# GD_Power_Meter_3.net
KiCad netlist of a schematic drawn in Altium Designer
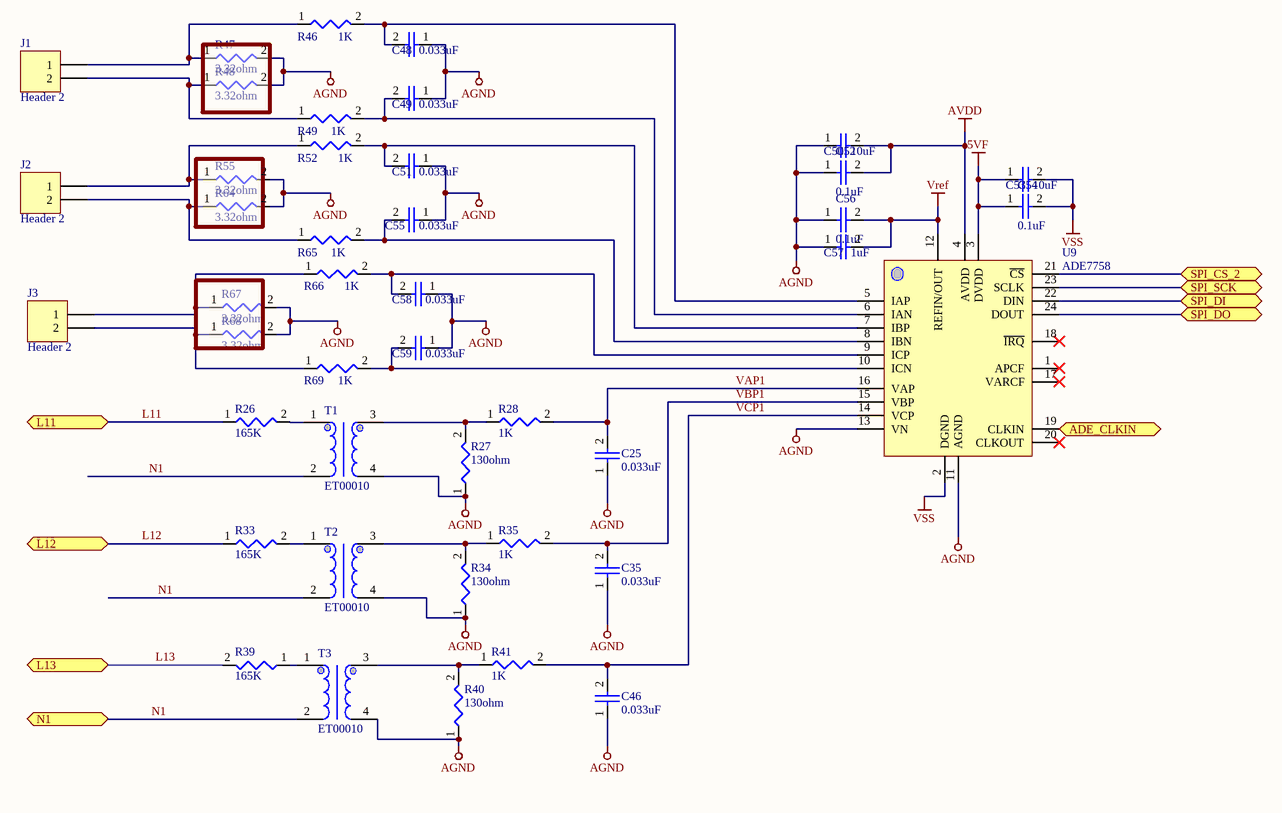
[diagram p0: GD_Power_Meter_3.SchDoc]

(export (version "E")
  (design (tool "Eeschema 10.0.6"))
  (components
    (comp (ref "C25")
      (value "0.033uF")
      (footprint "C0805")
      (description "CAP SMD X7R 50V 10% 0.033uF 0805 ROHS")
      (fields (field (name "MANUFACTURER") "Murata") (field (name "Comment") "CAP"))
      (libsource (lib "enlogic") (part "CAP"))
    )
    (comp (ref "C35")
      (value "0.033uF")
      (footprint "C0805")
      (description "CAP SMD X7R 50V 10% 0.033uF 0805 ROHS")
      (fields (field (name "MANUFACTURER") "Murata") (field (name "Comment") "CAP"))
      (libsource (lib "enlogic") (part "CAP"))
    )
    (comp (ref "C46")
      (value "0.033uF")
      (footprint "C0805")
      (description "CAP SMD X7R 50V 10% 0.033uF 0805 ROHS")
      (fields (field (name "MANUFACTURER") "Murata") (field (name "Comment") "CAP"))
      (libsource (lib "enlogic") (part "CAP"))
    )
    (comp (ref "C48")
      (value "0.033uF")
      (footprint "C0805")
      (description "CAP SMD X7R 50V 10% 0.033uF 0805 ROHS")
      (fields (field (name "MANUFACTURER") "Murata") (field (name "Comment") "CAP"))
      (libsource (lib "enlogic") (part "CAP"))
    )
    (comp (ref "C49")
      (value "0.033uF")
      (footprint "C0805")
      (description "CAP SMD X7R 50V 10% 0.033uF 0805 ROHS")
      (fields (field (name "MANUFACTURER") "Murata") (field (name "Comment") "CAP"))
      (libsource (lib "enlogic") (part "CAP"))
    )
    (comp (ref "C50")
      (value "10uF")
      (footprint "C0805")
      (description "CAP SMD CR X5R 16V 10% 10uF 0805 ROHS")
      (fields (field (name "MANUFACTURER") "Murata"))
      (libsource (lib "enlogic") (part "CAP"))
    )
    (comp (ref "C51")
      (value "0.033uF")
      (footprint "C0805")
      (description "CAP SMD X7R 50V 10% 0.033uF 0805 ROHS")
      (fields (field (name "MANUFACTURER") "Murata") (field (name "Comment") "CAP"))
      (libsource (lib "enlogic") (part "CAP"))
    )
    (comp (ref "C52")
      (value "0.1uF")
      (footprint "C0805")
      (description "CAP SMD CR X7R 50V 10% 0.1uF 0805 ROHS")
      (fields (field (name "MANUFACTURER") "YAGEO") (field (name "Comment") "CAP"))
      (libsource (lib "enlogic") (part "CAP"))
    )
    (comp (ref "C53")
      (value "10uF")
      (footprint "C0805")
      (description "CAP SMD CR X5R 16V 10% 10uF 0805 ROHS")
      (fields (field (name "MANUFACTURER") "Murata"))
      (libsource (lib "enlogic") (part "CAP"))
    )
    (comp (ref "C54")
      (value "0.1uF")
      (footprint "C0805")
      (description "CAP SMD CR X7R 50V 10% 0.1uF 0805 ROHS")
      (fields (field (name "MANUFACTURER") "YAGEO") (field (name "Comment") "CAP"))
      (libsource (lib "enlogic") (part "CAP"))
    )
    (comp (ref "C55")
      (value "0.033uF")
      (footprint "C0805")
      (description "CAP SMD X7R 50V 10% 0.033uF 0805 ROHS")
      (fields (field (name "MANUFACTURER") "Murata") (field (name "Comment") "CAP"))
      (libsource (lib "enlogic") (part "CAP"))
    )
    (comp (ref "C56")
      (value "0.1uF")
      (footprint "C0805")
      (description "CAP SMD CR X7R 50V 10% 0.1uF 0805 ROHS")
      (fields (field (name "MANUFACTURER") "YAGEO") (field (name "Comment") "CAP"))
      (libsource (lib "enlogic") (part "CAP"))
    )
    (comp (ref "C57")
      (value "1uF")
      (footprint "C0805")
      (description "CAP SMD CR X7R 50V 10% 1uF 0805 ROHS")
      (fields (field (name "MANUFACTURER") "YAGEO") (field (name "Comment") "CAP"))
      (libsource (lib "enlogic") (part "CAP"))
    )
    (comp (ref "C58")
      (value "0.033uF")
      (footprint "C0805")
      (description "CAP SMD X7R 50V 10% 0.033uF 0805 ROHS")
      (fields (field (name "MANUFACTURER") "Murata") (field (name "Comment") "CAP"))
      (libsource (lib "enlogic") (part "CAP"))
    )
    (comp (ref "C59")
      (value "0.033uF")
      (footprint "C0805")
      (description "CAP SMD X7R 50V 10% 0.033uF 0805 ROHS")
      (fields (field (name "MANUFACTURER") "Murata") (field (name "Comment") "CAP"))
      (libsource (lib "enlogic") (part "CAP"))
    )
    (comp (ref "J1")
      (value "Header 2")
      (footprint "533980271_sd")
      (description "CONNECTOR 1.25mm Pitch Header, Surface Mount, Vertical, Lead-Free, 2 Circuits")
      (fields (field (name "MANUFACTURER") "MOLEX"))
      (libsource (lib "enlogic") (part "Header 2"))
    )
    (comp (ref "J2")
      (value "Header 2")
      (footprint "533980271_sd")
      (description "CONNECTOR 1.25mm Pitch Header, Surface Mount, Vertical, Lead-Free, 2 Circuits")
      (fields (field (name "MANUFACTURER") "MOLEX"))
      (libsource (lib "enlogic") (part "Header 2"))
    )
    (comp (ref "J3")
      (value "Header 2")
      (footprint "533980271_sd")
      (description "CONNECTOR 1.25mm Pitch Header, Surface Mount, Vertical, Lead-Free, 2 Circuits")
      (fields (field (name "MANUFACTURER") "MOLEX"))
      (libsource (lib "enlogic") (part "Header 2"))
    )
    (comp (ref "R26")
      (value "165K")
      (footprint "MFR5W2P5")
      (description "RES Film Leaded 165K 0.5% 3W ROHS ±25ppm/℃ MFR1550")
      (fields (field (name "MANUFACTURER") "Viking") (field (name "Comment") "RES"))
      (libsource (lib "Enlogic") (part "RES"))
    )
    (comp (ref "R27")
      (value "130ohm")
      (footprint "R0805")
      (description "RES,THIN_FILM,130 ohm,0.5%	,1/10W,±25ppm/℃,ROHS,0805,SMD")
      (fields (field (name "MANUFACTURER") "VIKING") (field (name "Comment") "RES"))
      (libsource (lib "Enlogic") (part "RES"))
    )
    (comp (ref "R28")
      (value "1K")
      (footprint "R0805")
      (description "RES THICK_FILM SMD 1K 1% 1/8W ROHS 0805")
      (fields (field (name "MANUFACTURER") "YAGEO") (field (name "Comment") "RES"))
      (libsource (lib "Enlogic") (part "RES"))
    )
    (comp (ref "R33")
      (value "165K")
      (footprint "MFR5W2P5")
      (description "RES Film Leaded 165K 0.5% 3W ROHS ±25ppm/℃ MFR1550")
      (fields (field (name "MANUFACTURER") "Viking") (field (name "Comment") "RES"))
      (libsource (lib "Enlogic") (part "RES"))
    )
    (comp (ref "R34")
      (value "130ohm")
      (footprint "R0805")
      (description "RES,THIN_FILM,130 ohm,0.5%	,1/10W,±25ppm/℃,ROHS,0805,SMD")
      (fields (field (name "MANUFACTURER") "VIKING") (field (name "Comment") "RES"))
      (libsource (lib "Enlogic") (part "RES"))
    )
    (comp (ref "R35")
      (value "1K")
      (footprint "R0805")
      (description "RES THICK_FILM SMD 1K 1% 1/8W ROHS 0805")
      (fields (field (name "MANUFACTURER") "YAGEO") (field (name "Comment") "RES"))
      (libsource (lib "Enlogic") (part "RES"))
    )
    (comp (ref "R39")
      (value "165K")
      (footprint "MFR5W2P5")
      (description "RES Film Leaded 165K 0.5% 3W ROHS ±25ppm/℃ MFR1550")
      (fields (field (name "MANUFACTURER") "Viking") (field (name "Comment") "RES"))
      (libsource (lib "Enlogic") (part "RES"))
    )
    (comp (ref "R40")
      (value "130ohm")
      (footprint "R0805")
      (description "RES,THIN_FILM,130 ohm,0.5%	,1/10W,±25ppm/℃,ROHS,0805,SMD")
      (fields (field (name "MANUFACTURER") "VIKING") (field (name "Comment") "RES"))
      (libsource (lib "Enlogic") (part "RES"))
    )
    (comp (ref "R41")
      (value "1K")
      (footprint "R0805")
      (description "RES THICK_FILM SMD 1K 1% 1/8W ROHS 0805")
      (fields (field (name "MANUFACTURER") "YAGEO") (field (name "Comment") "RES"))
      (libsource (lib "Enlogic") (part "RES"))
    )
    (comp (ref "R46")
      (value "1K")
      (footprint "R0805")
      (description "RES THICK_FILM SMD 1K 1% 1/8W ROHS 0805")
      (fields (field (name "MANUFACTURER") "YAGEO") (field (name "Comment") "RES"))
      (libsource (lib "enlogic") (part "RES"))
    )
    (comp (ref "R47")
      (value "3.32ohm")
      (footprint "R0805")
      (description "RES THIN_FILM SMD 3.32 ohm 0.5% 1/8W ±50ppm/℃ ROHS 0805")
      (fields (field (name "MANUFACTURER") "YAGEO") (field (name "Comment") "RES"))
      (libsource (lib "Enlogic") (part "RES"))
    )
    (comp (ref "R48")
      (value "3.32ohm")
      (footprint "R0805")
      (description "RES THIN_FILM SMD 3.32 ohm 0.5% 1/8W ±50ppm/℃ ROHS 0805")
      (fields (field (name "MANUFACTURER") "YAGEO") (field (name "Comment") "RES"))
      (libsource (lib "Enlogic") (part "RES"))
    )
    (comp (ref "R49")
      (value "1K")
      (footprint "R0805")
      (description "RES THICK_FILM SMD 1K 1% 1/8W ROHS 0805")
      (fields (field (name "MANUFACTURER") "YAGEO") (field (name "Comment") "RES"))
      (libsource (lib "enlogic") (part "RES"))
    )
    (comp (ref "R52")
      (value "1K")
      (footprint "R0805")
      (description "RES THICK_FILM SMD 1K 1% 1/8W ROHS 0805")
      (fields (field (name "MANUFACTURER") "YAGEO") (field (name "Comment") "RES"))
      (libsource (lib "enlogic") (part "RES"))
    )
    (comp (ref "R55")
      (value "3.32ohm")
      (footprint "R0805")
      (description "RES THIN_FILM SMD 3.32 ohm 0.5% 1/8W ±50ppm/℃ ROHS 0805")
      (fields (field (name "MANUFACTURER") "YAGEO") (field (name "Comment") "RES"))
      (libsource (lib "Enlogic") (part "RES"))
    )
    (comp (ref "R64")
      (value "3.32ohm")
      (footprint "R0805")
      (description "RES THIN_FILM SMD 3.32 ohm 0.5% 1/8W ±50ppm/℃ ROHS 0805")
      (fields (field (name "MANUFACTURER") "YAGEO") (field (name "Comment") "RES"))
      (libsource (lib "Enlogic") (part "RES"))
    )
    (comp (ref "R65")
      (value "1K")
      (footprint "R0805")
      (description "RES THICK_FILM SMD 1K 1% 1/8W ROHS 0805")
      (fields (field (name "MANUFACTURER") "YAGEO") (field (name "Comment") "RES"))
      (libsource (lib "enlogic") (part "RES"))
    )
    (comp (ref "R66")
      (value "1K")
      (footprint "R0805")
      (description "RES THICK_FILM SMD 1K 1% 1/8W ROHS 0805")
      (fields (field (name "MANUFACTURER") "YAGEO") (field (name "Comment") "RES"))
      (libsource (lib "enlogic") (part "RES"))
    )
    (comp (ref "R67")
      (value "3.32ohm")
      (footprint "R0805")
      (description "RES THIN_FILM SMD 3.32 ohm 0.5% 1/8W ±50ppm/℃ ROHS 0805")
      (fields (field (name "MANUFACTURER") "YAGEO") (field (name "Comment") "RES"))
      (libsource (lib "Enlogic") (part "RES"))
    )
    (comp (ref "R68")
      (value "3.32ohm")
      (footprint "R0805")
      (description "RES THIN_FILM SMD 3.32 ohm 0.5% 1/8W ±50ppm/℃ ROHS 0805")
      (fields (field (name "MANUFACTURER") "YAGEO") (field (name "Comment") "RES"))
      (libsource (lib "Enlogic") (part "RES"))
    )
    (comp (ref "R69")
      (value "1K")
      (footprint "R0805")
      (description "RES THICK_FILM SMD 1K 1% 1/8W ROHS 0805")
      (fields (field (name "MANUFACTURER") "YAGEO") (field (name "Comment") "RES"))
      (libsource (lib "enlogic") (part "RES"))
    )
    (comp (ref "T1")
      (value "ET00010")
      (footprint "ZMPT107")
      (description "Voltage transformer,2mA/2mA,THT,ROHS")
      (fields (field (name "MANUFACTURER") "ZEMING"))
      (libsource (lib "Enlogic") (part "ZMPT107"))
    )
    (comp (ref "T2")
      (value "ET00010")
      (footprint "ZMPT107")
      (description "Voltage transformer,2mA/2mA,THT,ROHS")
      (fields (field (name "MANUFACTURER") "ZEMING"))
      (libsource (lib "Enlogic") (part "ZMPT107"))
    )
    (comp (ref "T3")
      (value "ET00010")
      (footprint "ZMPT107")
      (description "Voltage transformer,2mA/2mA,THT,ROHS")
      (fields (field (name "MANUFACTURER") "ZEMING"))
      (libsource (lib "Enlogic") (part "ZMPT107"))
    )
    (comp (ref "U9")
      (value "ADE7758")
      (footprint "SOIC24-W")
      (description "IC Energy Measurement,Irms,VA,VAR,Vrms,Watt,Output:Pulsed&SPI,SOIC_W-24,ROHS")
      (fields (field (name "MANUFACTURER") "ANALOG DEVICES"))
      (libsource (lib "enlogic") (part "ADE7758"))
    )
  )
  (nets
    (net (code "1") (name "/ADE_CLKIN") (class "Default")
      (node (ref "U9") (pin "19") (pinfunction "CLKIN_19") (pintype "passive"))
    )
    (net (code "2") (name "/L11") (class "Default")
      (node (ref "R26") (pin "1") (pinfunction "1_1") (pintype "passive"))
    )
    (net (code "3") (name "/L12") (class "Default")
      (node (ref "R33") (pin "1") (pinfunction "1_1") (pintype "passive"))
    )
    (net (code "4") (name "/L13") (class "Default")
      (node (ref "R39") (pin "2") (pinfunction "2_2") (pintype "passive"))
    )
    (net (code "5") (name "/N1") (class "Default")
      (node (ref "T1") (pin "2") (pinfunction "2_2") (pintype "passive"))
      (node (ref "T2") (pin "2") (pinfunction "2_2") (pintype "passive"))
      (node (ref "T3") (pin "2") (pinfunction "2_2") (pintype "passive"))
    )
    (net (code "6") (name "/SPI_CS_2") (class "Default")
      (node (ref "U9") (pin "21") (pinfunction "~{CS}_21") (pintype "passive"))
    )
    (net (code "7") (name "/SPI_DI") (class "Default")
      (node (ref "U9") (pin "22") (pinfunction "DIN_22") (pintype "passive"))
    )
    (net (code "8") (name "/SPI_DO") (class "Default")
      (node (ref "U9") (pin "24") (pinfunction "DOUT_24") (pintype "passive"))
    )
    (net (code "9") (name "/SPI_SCK") (class "Default")
      (node (ref "U9") (pin "23") (pinfunction "SCLK_23") (pintype "passive"))
    )
    (net (code "10") (name "/VAP1") (class "Default")
      (node (ref "C25") (pin "2") (pinfunction "2_2") (pintype "passive"))
      (node (ref "R28") (pin "2") (pinfunction "2_2") (pintype "passive"))
      (node (ref "U9") (pin "16") (pinfunction "VAP_16") (pintype "passive"))
    )
    (net (code "11") (name "/VBP1") (class "Default")
      (node (ref "C35") (pin "2") (pinfunction "2_2") (pintype "passive"))
      (node (ref "R35") (pin "2") (pinfunction "2_2") (pintype "passive"))
      (node (ref "U9") (pin "15") (pinfunction "VBP_15") (pintype "passive"))
    )
    (net (code "12") (name "/VCP1") (class "Default")
      (node (ref "C46") (pin "2") (pinfunction "2_2") (pintype "passive"))
      (node (ref "R41") (pin "2") (pinfunction "2_2") (pintype "passive"))
      (node (ref "U9") (pin "14") (pinfunction "VCP_14") (pintype "passive"))
    )
    (net (code "13") (name "5VF") (class "Default")
      (node (ref "C53") (pin "1") (pinfunction "1_1") (pintype "passive"))
      (node (ref "C54") (pin "1") (pinfunction "1_1") (pintype "passive"))
      (node (ref "U9") (pin "3") (pinfunction "DVDD_3") (pintype "passive"))
    )
    (net (code "14") (name "AGND") (class "Default")
      (node (ref "C25") (pin "1") (pinfunction "1_1") (pintype "passive"))
      (node (ref "C35") (pin "1") (pinfunction "1_1") (pintype "passive"))
      (node (ref "C46") (pin "1") (pinfunction "1_1") (pintype "passive"))
      (node (ref "C48") (pin "1") (pinfunction "1_1") (pintype "passive"))
      (node (ref "C49") (pin "1") (pinfunction "1_1") (pintype "passive"))
      (node (ref "C50") (pin "1") (pinfunction "1_1") (pintype "passive"))
      (node (ref "C51") (pin "1") (pinfunction "1_1") (pintype "passive"))
      (node (ref "C52") (pin "1") (pinfunction "1_1") (pintype "passive"))
      (node (ref "C55") (pin "1") (pinfunction "1_1") (pintype "passive"))
      (node (ref "C56") (pin "1") (pinfunction "1_1") (pintype "passive"))
      (node (ref "C57") (pin "1") (pinfunction "1_1") (pintype "passive"))
      (node (ref "C58") (pin "1") (pinfunction "1_1") (pintype "passive"))
      (node (ref "C59") (pin "1") (pinfunction "1_1") (pintype "passive"))
      (node (ref "R27") (pin "1") (pinfunction "1_1") (pintype "passive"))
      (node (ref "R34") (pin "1") (pinfunction "1_1") (pintype "passive"))
      (node (ref "R40") (pin "1") (pinfunction "1_1") (pintype "passive"))
      (node (ref "R47") (pin "2") (pinfunction "2_2") (pintype "passive"))
      (node (ref "R48") (pin "2") (pinfunction "2_2") (pintype "passive"))
      (node (ref "R55") (pin "2") (pinfunction "2_2") (pintype "passive"))
      (node (ref "R64") (pin "2") (pinfunction "2_2") (pintype "passive"))
      (node (ref "R67") (pin "2") (pinfunction "2_2") (pintype "passive"))
      (node (ref "R68") (pin "2") (pinfunction "2_2") (pintype "passive"))
      (node (ref "T1") (pin "4") (pinfunction "4_4") (pintype "passive"))
      (node (ref "T2") (pin "4") (pinfunction "4_4") (pintype "passive"))
      (node (ref "T3") (pin "4") (pinfunction "4_4") (pintype "passive"))
      (node (ref "U9") (pin "11") (pinfunction "AGND_11") (pintype "passive"))
      (node (ref "U9") (pin "13") (pinfunction "VN_13") (pintype "passive"))
    )
    (net (code "15") (name "AVDD") (class "Default")
      (node (ref "C50") (pin "2") (pinfunction "2_2") (pintype "passive"))
      (node (ref "C52") (pin "2") (pinfunction "2_2") (pintype "passive"))
      (node (ref "U9") (pin "4") (pinfunction "AVDD_4") (pintype "passive"))
    )
    (net (code "16") (name "Net-(J1-Pad1)") (class "Default")
      (node (ref "J1") (pin "1") (pinfunction "1_1") (pintype "passive"))
      (node (ref "R46") (pin "1") (pinfunction "1_1") (pintype "passive"))
      (node (ref "R47") (pin "1") (pinfunction "1_1") (pintype "passive"))
    )
    (net (code "17") (name "Net-(J1-Pad2)") (class "Default")
      (node (ref "J1") (pin "2") (pinfunction "2_2") (pintype "passive"))
      (node (ref "R48") (pin "1") (pinfunction "1_1") (pintype "passive"))
      (node (ref "R49") (pin "1") (pinfunction "1_1") (pintype "passive"))
    )
    (net (code "18") (name "Net-(J2-Pad1)") (class "Default")
      (node (ref "J2") (pin "1") (pinfunction "1_1") (pintype "passive"))
      (node (ref "R52") (pin "1") (pinfunction "1_1") (pintype "passive"))
      (node (ref "R55") (pin "1") (pinfunction "1_1") (pintype "passive"))
    )
    (net (code "19") (name "Net-(J2-Pad2)") (class "Default")
      (node (ref "J2") (pin "2") (pinfunction "2_2") (pintype "passive"))
      (node (ref "R64") (pin "1") (pinfunction "1_1") (pintype "passive"))
      (node (ref "R65") (pin "1") (pinfunction "1_1") (pintype "passive"))
    )
    (net (code "20") (name "Net-(J3-Pad1)") (class "Default")
      (node (ref "J3") (pin "1") (pinfunction "1_1") (pintype "passive"))
      (node (ref "R66") (pin "1") (pinfunction "1_1") (pintype "passive"))
      (node (ref "R67") (pin "1") (pinfunction "1_1") (pintype "passive"))
    )
    (net (code "21") (name "Net-(J3-Pad2)") (class "Default")
      (node (ref "J3") (pin "2") (pinfunction "2_2") (pintype "passive"))
      (node (ref "R68") (pin "1") (pinfunction "1_1") (pintype "passive"))
      (node (ref "R69") (pin "1") (pinfunction "1_1") (pintype "passive"))
    )
    (net (code "22") (name "Net-(R26-Pad2)") (class "Default")
      (node (ref "R26") (pin "2") (pinfunction "2_2") (pintype "passive"))
      (node (ref "T1") (pin "1") (pinfunction "1_1") (pintype "passive"))
    )
    (net (code "23") (name "Net-(R27-Pad2)") (class "Default")
      (node (ref "R27") (pin "2") (pinfunction "2_2") (pintype "passive"))
      (node (ref "R28") (pin "1") (pinfunction "1_1") (pintype "passive"))
      (node (ref "T1") (pin "3") (pinfunction "3_3") (pintype "passive"))
    )
    (net (code "24") (name "Net-(R33-Pad2)") (class "Default")
      (node (ref "R33") (pin "2") (pinfunction "2_2") (pintype "passive"))
      (node (ref "T2") (pin "1") (pinfunction "1_1") (pintype "passive"))
    )
    (net (code "25") (name "Net-(R34-Pad2)") (class "Default")
      (node (ref "R34") (pin "2") (pinfunction "2_2") (pintype "passive"))
      (node (ref "R35") (pin "1") (pinfunction "1_1") (pintype "passive"))
      (node (ref "T2") (pin "3") (pinfunction "3_3") (pintype "passive"))
    )
    (net (code "26") (name "Net-(R39-Pad1)") (class "Default")
      (node (ref "R39") (pin "1") (pinfunction "1_1") (pintype "passive"))
      (node (ref "T3") (pin "1") (pinfunction "1_1") (pintype "passive"))
    )
    (net (code "27") (name "Net-(R40-Pad2)") (class "Default")
      (node (ref "R40") (pin "2") (pinfunction "2_2") (pintype "passive"))
      (node (ref "R41") (pin "1") (pinfunction "1_1") (pintype "passive"))
      (node (ref "T3") (pin "3") (pinfunction "3_3") (pintype "passive"))
    )
    (net (code "28") (name "Net-(U9-IAN)") (class "Default")
      (node (ref "C49") (pin "2") (pinfunction "2_2") (pintype "passive"))
      (node (ref "R49") (pin "2") (pinfunction "2_2") (pintype "passive"))
      (node (ref "U9") (pin "6") (pinfunction "IAN_6") (pintype "passive"))
    )
    (net (code "29") (name "Net-(U9-IAP)") (class "Default")
      (node (ref "C48") (pin "2") (pinfunction "2_2") (pintype "passive"))
      (node (ref "R46") (pin "2") (pinfunction "2_2") (pintype "passive"))
      (node (ref "U9") (pin "5") (pinfunction "IAP_5") (pintype "passive"))
    )
    (net (code "30") (name "Net-(U9-IBN)") (class "Default")
      (node (ref "C55") (pin "2") (pinfunction "2_2") (pintype "passive"))
      (node (ref "R65") (pin "2") (pinfunction "2_2") (pintype "passive"))
      (node (ref "U9") (pin "8") (pinfunction "IBN_8") (pintype "passive"))
    )
    (net (code "31") (name "Net-(U9-IBP)") (class "Default")
      (node (ref "C51") (pin "2") (pinfunction "2_2") (pintype "passive"))
      (node (ref "R52") (pin "2") (pinfunction "2_2") (pintype "passive"))
      (node (ref "U9") (pin "7") (pinfunction "IBP_7") (pintype "passive"))
    )
    (net (code "32") (name "Net-(U9-ICN)") (class "Default")
      (node (ref "C59") (pin "2") (pinfunction "2_2") (pintype "passive"))
      (node (ref "R69") (pin "2") (pinfunction "2_2") (pintype "passive"))
      (node (ref "U9") (pin "10") (pinfunction "ICN_10") (pintype "passive"))
    )
    (net (code "33") (name "Net-(U9-ICP)") (class "Default")
      (node (ref "C58") (pin "2") (pinfunction "2_2") (pintype "passive"))
      (node (ref "R66") (pin "2") (pinfunction "2_2") (pintype "passive"))
      (node (ref "U9") (pin "9") (pinfunction "ICP_9") (pintype "passive"))
    )
    (net (code "34") (name "VSS") (class "Default")
      (node (ref "C53") (pin "2") (pinfunction "2_2") (pintype "passive"))
      (node (ref "C54") (pin "2") (pinfunction "2_2") (pintype "passive"))
      (node (ref "U9") (pin "2") (pinfunction "DGND_2") (pintype "passive"))
    )
    (net (code "35") (name "Vref") (class "Default")
      (node (ref "C56") (pin "2") (pinfunction "2_2") (pintype "passive"))
      (node (ref "C57") (pin "2") (pinfunction "2_2") (pintype "passive"))
      (node (ref "U9") (pin "12") (pinfunction "REFIN/OUT_12") (pintype "passive"))
    )
    (net (code "36") (name "unconnected-(U9-APCF-Pad1)") (class "Default")
      (node (ref "U9") (pin "1") (pinfunction "APCF_1") (pintype "passive+no_connect"))
    )
    (net (code "37") (name "unconnected-(U9-CLKOUT-Pad20)") (class "Default")
      (node (ref "U9") (pin "20") (pinfunction "CLKOUT_20") (pintype "passive+no_connect"))
    )
    (net (code "38") (name "unconnected-(U9-VARCF-Pad17)") (class "Default")
      (node (ref "U9") (pin "17") (pinfunction "VARCF_17") (pintype "passive+no_connect"))
    )
    (net (code "39") (name "unconnected-(U9-~{IRQ}-Pad18)") (class "Default")
      (node (ref "U9") (pin "18") (pinfunction "~{IRQ}_18") (pintype "passive+no_connect"))
    )
  )
)
